# pt4115.net
KiCad netlist of a schematic drawn in EAGLE
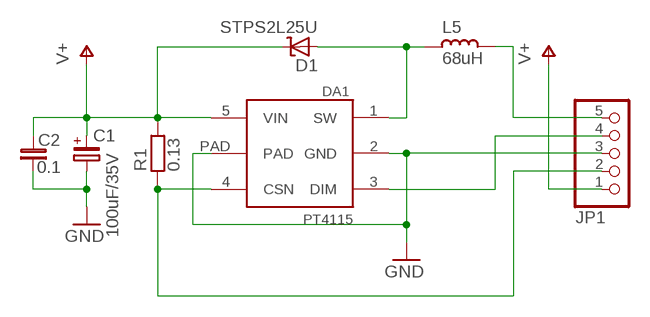
[diagram p0: schematic, sheet 1]

(export (version "E")
  (design (tool "Eeschema 10.0.6"))
  (components
    (comp (ref "C1")
      (value "100uF/35V")
      (footprint "eagle-import:CE-025X060")
      (libsource (lib "eagle-import") (part "CP_E-025X060"))
    )
    (comp (ref "C2")
      (value "0.1")
      (footprint "eagle-import:C0805")
      (libsource (lib "eagle-import") (part "C_0805"))
    )
    (comp (ref "D1")
      (value "STPS2L25U")
      (footprint "eagle-import:SMB_1")
      (libsource (lib "eagle-import") (part "STPS2L25U"))
    )
    (comp (ref "DA1")
      (value "PT4115")
      (footprint "eagle-import:SOT89-5")
      (libsource (lib "eagle-import") (part "PT4115"))
    )
    (comp (ref "JP1")
      (value "PINHD-1X5_2.54-90°")
      (footprint "eagle-import:1X05_90")
      (libsource (lib "eagle-import") (part "PINHD-1X5_2.54-90°"))
    )
    (comp (ref "L5")
      (value "68uH")
      (footprint "eagle-import:CD54")
      (libsource (lib "eagle-import") (part "L_CD54"))
    )
    (comp (ref "R1")
      (value "0.13")
      (footprint "eagle-import:R1206")
      (libsource (lib "eagle-import") (part "R_1206"))
    )
  )
  (nets
    (net (code "1") (name "GND") (class "Default")
      (node (ref "C1") (pin "-") (pinfunction "-_-") (pintype "passive"))
      (node (ref "C2") (pin "2") (pinfunction "2_2") (pintype "passive"))
      (node (ref "DA1") (pin "2") (pinfunction "GND_2") (pintype "bidirectional"))
      (node (ref "DA1") (pin "PAD") (pinfunction "PAD_PAD") (pintype "bidirectional"))
      (node (ref "JP1") (pin "3") (pinfunction "3_3") (pintype "passive"))
    )
    (net (code "2") (name "Net-(DA1-CSN)") (class "Default")
      (node (ref "DA1") (pin "4") (pinfunction "CSN_4") (pintype "bidirectional"))
      (node (ref "JP1") (pin "2") (pinfunction "2_2") (pintype "passive"))
      (node (ref "R1") (pin "1") (pinfunction "1_1") (pintype "passive"))
    )
    (net (code "3") (name "Net-(DA1-DIM)") (class "Default")
      (node (ref "DA1") (pin "3") (pinfunction "DIM_3") (pintype "bidirectional"))
      (node (ref "JP1") (pin "4") (pinfunction "4_4") (pintype "passive"))
    )
    (net (code "4") (name "Net-(DA1-SW)") (class "Default")
      (node (ref "D1") (pin "A") (pinfunction "A_A") (pintype "passive"))
      (node (ref "DA1") (pin "1") (pinfunction "SW_1") (pintype "bidirectional"))
      (node (ref "L5") (pin "2") (pinfunction "2_2") (pintype "passive"))
    )
    (net (code "5") (name "Net-(JP1-Pad5)") (class "Default")
      (node (ref "JP1") (pin "5") (pinfunction "5_5") (pintype "passive"))
      (node (ref "L5") (pin "1") (pinfunction "1_1") (pintype "passive"))
    )
    (net (code "6") (name "V+") (class "Default")
      (node (ref "C1") (pin "+") (pinfunction "+_+") (pintype "passive"))
      (node (ref "C2") (pin "1") (pinfunction "1_1") (pintype "passive"))
      (node (ref "D1") (pin "C") (pinfunction "C_C") (pintype "passive"))
      (node (ref "DA1") (pin "5") (pinfunction "VIN_5") (pintype "bidirectional"))
      (node (ref "JP1") (pin "1") (pinfunction "1_1") (pintype "passive"))
      (node (ref "R1") (pin "2") (pinfunction "2_2") (pintype "passive"))
    )
  )
)
